# SW108_0713.net
KiCad netlist of a schematic drawn in Altium Designer
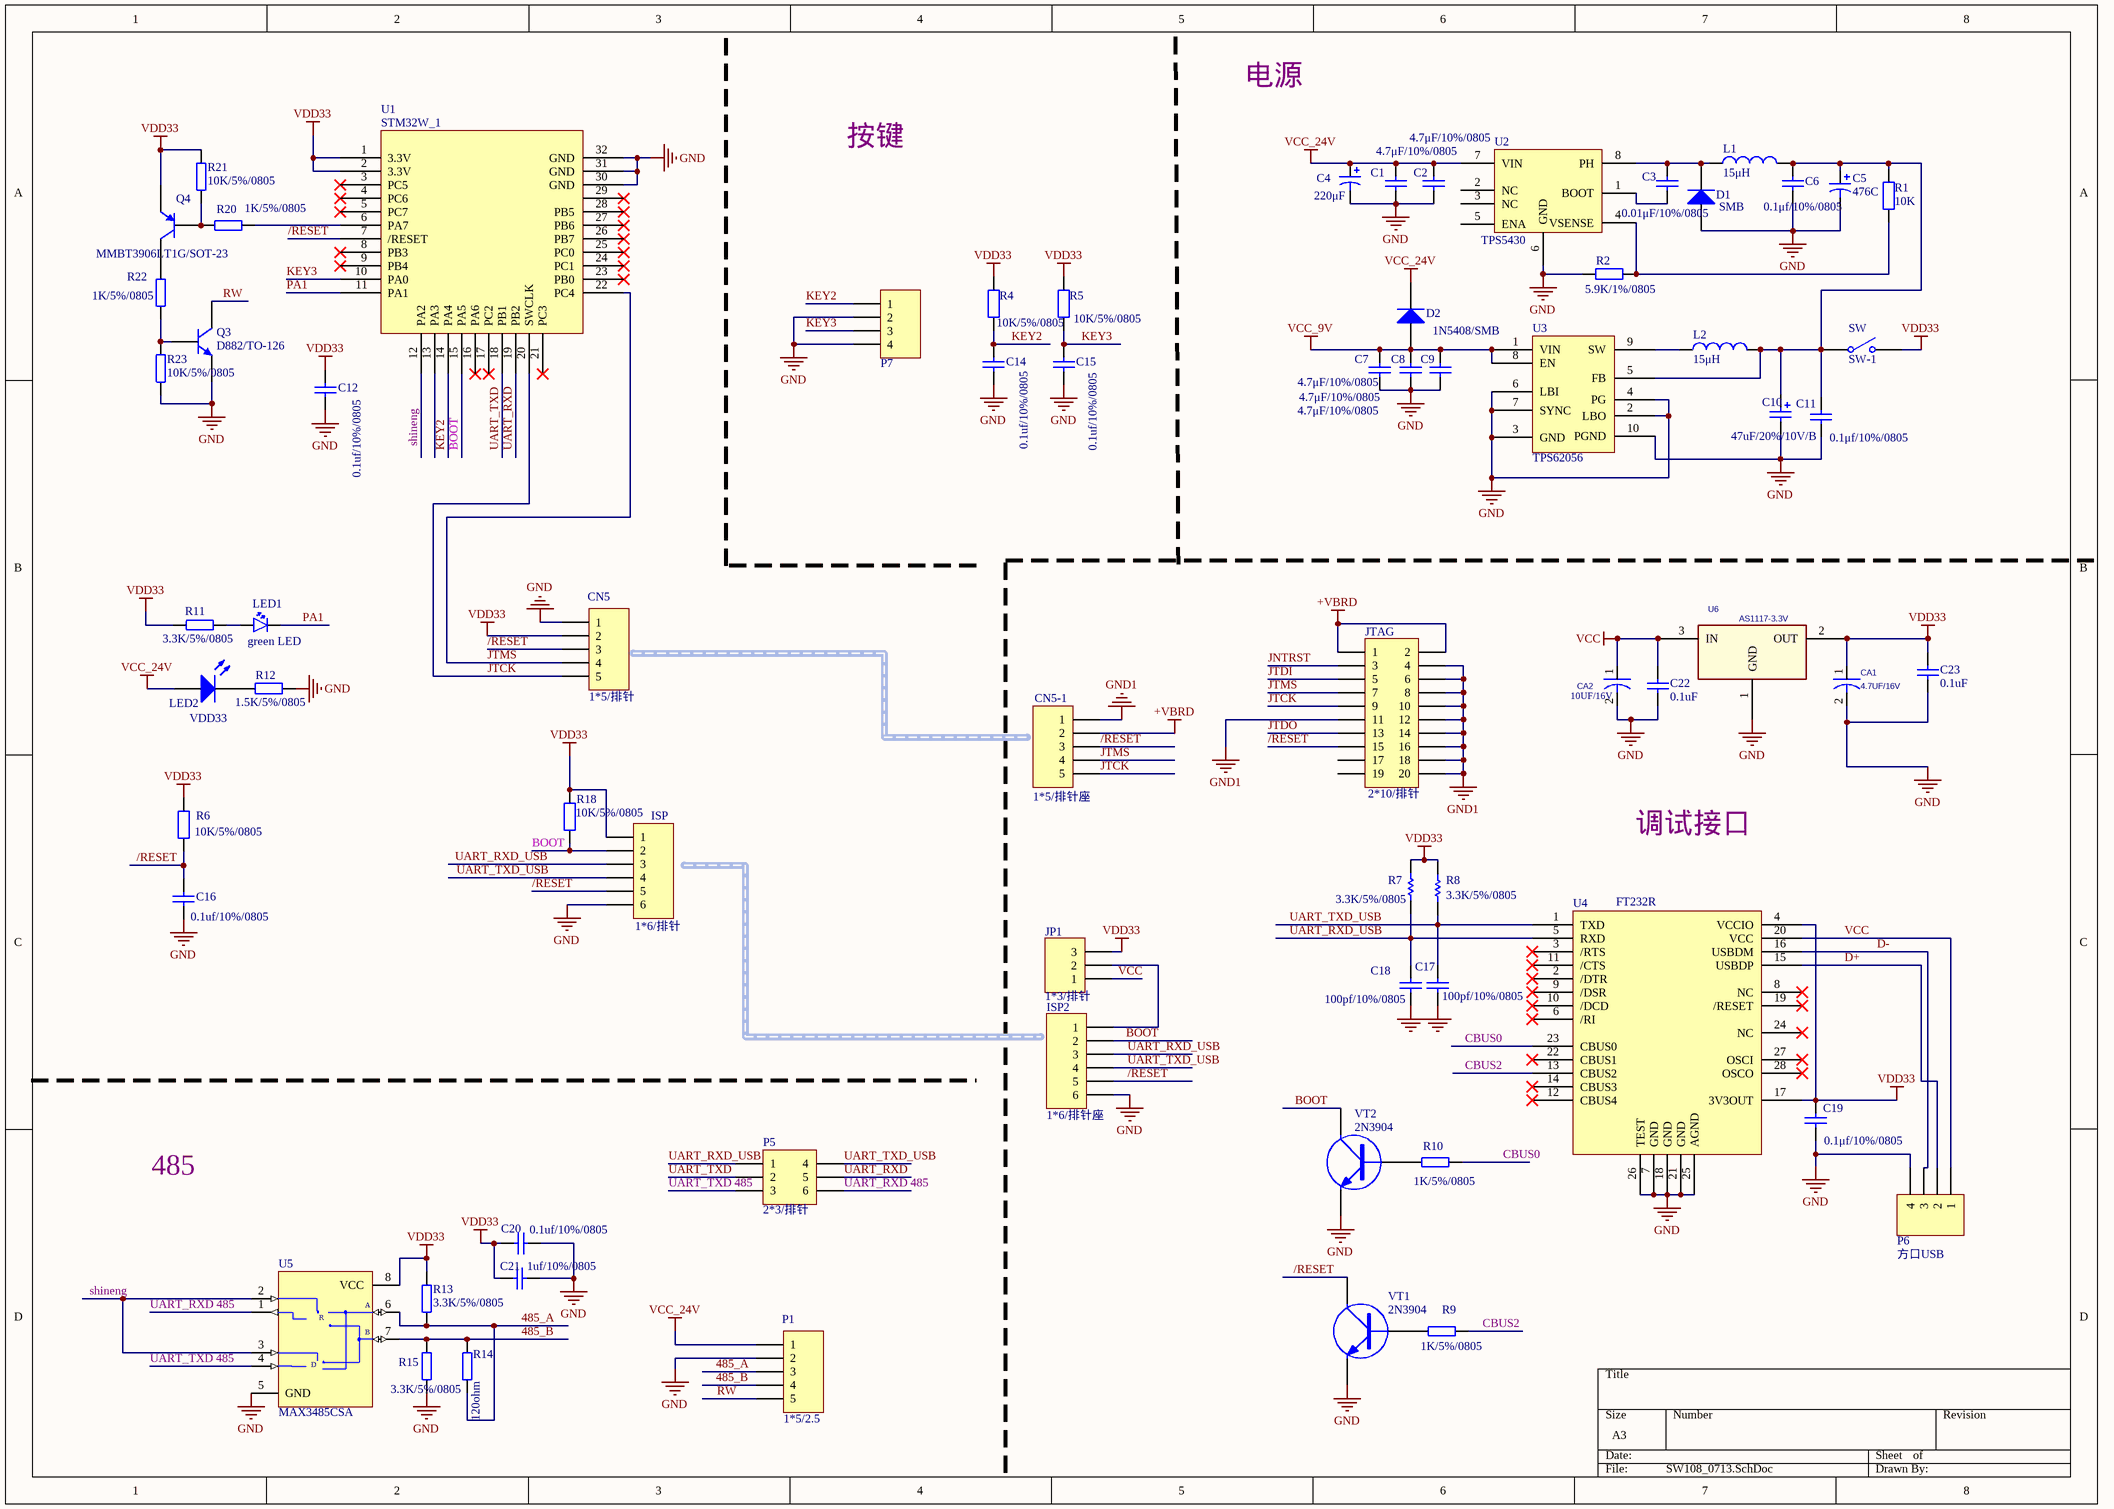
[diagram p0: SW108_0713.SchDoc]

(export (version "E")
  (design (tool "Eeschema 10.0.6"))
  (components
    (comp (ref "C1")
      (value "4.7μF/10%/0805")
      (footprint "C-0805")
      (description "Capacitor")
      (fields (field (name "PUBLISHER") "Altium Limited"))
      (libsource (lib "Miscellaneous Devices") (part "Cap"))
    )
    (comp (ref "C2")
      (value "4.7μF/10%/0805")
      (footprint "C-0805")
      (description "Capacitor")
      (fields (field (name "PUBLISHER") "Altium Limited"))
      (libsource (lib "Miscellaneous Devices") (part "Cap"))
    )
    (comp (ref "C3")
      (value "0.01μF/10%/0805")
      (footprint "C-0805")
      (description "Capacitor")
      (fields (field (name "PUBLISHER") "Altium Limited"))
      (libsource (lib "Miscellaneous Devices") (part "Cap"))
    )
    (comp (ref "C4")
      (value "220μF")
      (footprint "CZ3.0/6.5")
      (description "Polarized Capacitor (Radial)")
      (fields (field (name "PUBLISHER") "Altium Limited"))
      (libsource (lib "Miscellaneous Devices") (part "Cap Pol1"))
    )
    (comp (ref "C5")
      (value "476C")
      (footprint "C-TAN-D")
      (description "Polarized Capacitor (Radial)")
      (fields (field (name "PUBLISHER") "Altium Limited"))
      (libsource (lib "Miscellaneous Devices") (part "Cap Pol1"))
    )
    (comp (ref "C6")
      (value "0.1μf/10%/0805")
      (footprint "C-0805")
      (description "Capacitor")
      (fields (field (name "PUBLISHER") "Altium Limited"))
      (libsource (lib "Miscellaneous Devices") (part "Cap"))
    )
    (comp (ref "C7")
      (value "4.7μF/10%/0805")
      (footprint "C-0805")
      (description "Capacitor")
      (fields (field (name "PUBLISHER") "Altium Limited"))
      (libsource (lib "Miscellaneous Devices") (part "Cap"))
    )
    (comp (ref "C8")
      (value "4.7μF/10%/0805")
      (footprint "C-0805")
      (description "Capacitor")
      (fields (field (name "PUBLISHER") "Altium Limited"))
      (libsource (lib "Miscellaneous Devices") (part "Cap"))
    )
    (comp (ref "C9")
      (value "4.7μF/10%/0805")
      (footprint "C-0805")
      (description "Capacitor")
      (fields (field (name "PUBLISHER") "Altium Limited"))
      (libsource (lib "Miscellaneous Devices") (part "Cap"))
    )
    (comp (ref "C10")
      (value "47uF/20%/10V/B")
      (footprint "C-TAN-B")
      (libsource (lib "浙江关西电机数据库") (part "CAP_polarity"))
    )
    (comp (ref "C11")
      (value "0.1μf/10%/0805")
      (footprint "C-0805")
      (description "Capacitor")
      (fields (field (name "PUBLISHER") "Altium Limited"))
      (libsource (lib "Miscellaneous Devices") (part "Cap"))
    )
    (comp (ref "C12")
      (value "0.1uf/10%/0805")
      (footprint "C-0805")
      (description "Capacitor")
      (fields (field (name "PUBLISHER") "Altium Limited"))
      (libsource (lib "Miscellaneous Devices") (part "Cap"))
    )
    (comp (ref "C14")
      (value "0.1uf/10%/0805")
      (footprint "C-0805")
      (description "Capacitor")
      (fields (field (name "PUBLISHER") "Altium Limited"))
      (libsource (lib "Miscellaneous Devices") (part "Cap"))
    )
    (comp (ref "C15")
      (value "0.1uf/10%/0805")
      (footprint "C-0805")
      (description "Capacitor")
      (fields (field (name "PUBLISHER") "Altium Limited"))
      (libsource (lib "Miscellaneous Devices") (part "Cap"))
    )
    (comp (ref "C16")
      (value "0.1uf/10%/0805")
      (footprint "C-0805")
      (description "Capacitor")
      (fields (field (name "PUBLISHER") "Altium Limited"))
      (libsource (lib "Miscellaneous Devices") (part "Cap"))
    )
    (comp (ref "C17")
      (value "100pf/10%/0805")
      (footprint "C-0805")
      (description "Capacitor")
      (fields (field (name "PUBLISHER") "Altium Limited"))
      (libsource (lib "Miscellaneous Devices") (part "Cap"))
    )
    (comp (ref "C18")
      (value "100pf/10%/0805")
      (footprint "C-0805")
      (description "Capacitor")
      (fields (field (name "PUBLISHER") "Altium Limited"))
      (libsource (lib "Miscellaneous Devices") (part "Cap"))
    )
    (comp (ref "C19")
      (value "0.1μf/10%/0805")
      (footprint "C-0805")
      (description "Capacitor")
      (fields (field (name "PUBLISHER") "Altium Limited"))
      (libsource (lib "Miscellaneous Devices") (part "Cap"))
    )
    (comp (ref "C20")
      (value "0.1uf/10%/0805")
      (footprint "C-0805")
      (description "Capacitor")
      (fields (field (name "PUBLISHER") "Altium Limited"))
      (libsource (lib "Miscellaneous Devices") (part "Cap"))
    )
    (comp (ref "C21")
      (value "1uf/10%/0805")
      (footprint "C-0805")
      (description "Capacitor")
      (fields (field (name "PUBLISHER") "Altium Limited"))
      (libsource (lib "Miscellaneous Devices") (part "Cap"))
    )
    (comp (ref "C22")
      (value "0.1uF")
      (footprint "C0805")
      (description "Capacitor")
      (fields (field (name "PUBLISHER") "Altium Limited"))
      (libsource (lib "Miscellaneous Devices") (part "Cap"))
    )
    (comp (ref "C23")
      (value "0.1uF")
      (footprint "C0805")
      (description "Capacitor")
      (fields (field (name "PUBLISHER") "Altium Limited"))
      (libsource (lib "Miscellaneous Devices") (part "Cap"))
    )
    (comp (ref "CA1") (value "4.7UF/16V") (footprint "3528cap") (libsource (lib "v3") (part "ECAP")))
    (comp (ref "CA2") (value "10UF/16V") (footprint "3528Cap") (libsource (lib "v3") (part "ECAP")))
    (comp (ref "CN5") (value "1*5/排针") (footprint "PIN-S-2.54-1*5") (libsource (lib "") (part "Header1*5_1")))
    (comp (ref "CN5-1")
      (value "1*5/排针座")
      (footprint "PIN-S-2.54-1*5")
      (libsource (lib "SCHLIBRARIES") (part "Header1*5"))
    )
    (comp (ref "D1")
      (value "SMB")
      (footprint "SMB")
      (description "3 Amp Medium Power Silicon Rectifier Diode")
      (fields (field (name "PUBLISHER") "Altium Limited"))
      (libsource (lib "Miscellaneous Devices") (part "Diode 1N5408"))
    )
    (comp (ref "D2")
      (value "1N5408/SMB")
      (footprint "smb")
      (description "3 Amp Medium Power Silicon Rectifier Diode")
      (fields (field (name "PUBLISHER") "Altium Limited"))
      (libsource (lib "Miscellaneous Devices") (part "Diode 1N5408"))
    )
    (comp (ref "ISP")
      (value "1*6/排针")
      (footprint "PIN-S-2.54-1*6")
      (libsource (lib "SCHLIBRARIES") (part "Header1*6"))
    )
    (comp (ref "ISP2")
      (value "1*6/排针座")
      (footprint "PIN-S-2.54-1*6")
      (libsource (lib "") (part "Header1*6_1"))
    )
    (comp (ref "JP1")
      (value "1*3/排针")
      (footprint "PIN-S-2.54-1*3")
      (libsource (lib "SCHLIBRARIES") (part "Header1*3"))
    )
    (comp (ref "JTAG")
      (value "2*10/排针")
      (footprint "IDC-20")
      (libsource (lib "SCHLIBRARIES") (part "Header2*10"))
    )
    (comp (ref "L1")
      (value "15μH")
      (footprint "GSDS104C2")
      (description "Inductor")
      (fields (field (name "PUBLISHER") "Altium Limited"))
      (libsource (lib "Miscellaneous Devices") (part "Inductor"))
    )
    (comp (ref "L2")
      (value "15μH")
      (footprint "GSDS104C2")
      (description "Inductor")
      (fields (field (name "PUBLISHER") "Altium Limited"))
      (libsource (lib "Miscellaneous Devices") (part "Inductor"))
    )
    (comp (ref "LED1") (value "green LED") (footprint "LED-φ3") (libsource (lib "Haze") (part "LED")))
    (comp (ref "LED2")
      (value "VDD33")
      (footprint "LED-φ3")
      (description "Typical BLUE SiC LED")
      (fields (field (name "PUBLISHER") "Altium Limited"))
      (libsource (lib "Miscellaneous Devices") (part "LED3"))
    )
    (comp (ref "P1") (value "1*5/2.5") (footprint "PIN-S-2.54-1*5") (libsource (lib "") (part "Header1*5_1")))
    (comp (ref "P5")
      (value "2*3/排针")
      (footprint "HDR2X3_CEN")
      (description "Header, 3-Pin, Dual row")
      (fields (field (name "PUBLISHER") "Altium Limited"))
      (libsource (lib "Miscellaneous Connectors") (part "Header 3X2A"))
    )
    (comp (ref "P6")
      (value "方口USB")
      (footprint "USB_B_90D")
      (description "Header, 4-Pin")
      (fields (field (name "PUBLISHER") "Altium Limited"))
      (libsource (lib "Miscellaneous Connectors") (part "Header 4"))
    )
    (comp (ref "P7")
      (value "Header1*4")
      (footprint "PIN-S-2.54-1*4")
      (libsource (lib "SCHLIBRARIES") (part "Header1*4"))
    )
    (comp (ref "Q3")
      (value "D882/TO-126")
      (footprint "TO-126")
      (libsource (lib "SCHLIBRARIES") (part "NPN-1E2C3B"))
    )
    (comp (ref "Q4")
      (value "MMBT3906LT1G/SOT-23")
      (footprint "SOT-23")
      (fields (field (name "PART NUMBER") "ASQ-0009BA") (field (name "型号") "MMBT3906LT1G/SOT-23"))
      (libsource (lib "浙江关西电机数据库") (part "PNP_1B2E3C"))
    )
    (comp (ref "R1")
      (value "10K")
      (footprint "R-0805")
      (description "Resistor")
      (fields (field (name "PUBLISHER") "Altium Limited"))
      (libsource (lib "") (part "Res2_1"))
    )
    (comp (ref "R2")
      (value "5.9K/1%/0805")
      (footprint "R-0805")
      (description "Resistor")
      (fields (field (name "PUBLISHER") "Altium Limited"))
      (libsource (lib "Miscellaneous Devices") (part "Res2"))
    )
    (comp (ref "R4")
      (value "10K/5%/0805")
      (footprint "R-0805")
      (description "Resistor")
      (fields (field (name "PUBLISHER") "Altium Limited"))
      (libsource (lib "") (part "Res2_1"))
    )
    (comp (ref "R5")
      (value "10K/5%/0805")
      (footprint "R-0805")
      (description "Resistor")
      (fields (field (name "PUBLISHER") "Altium Limited"))
      (libsource (lib "") (part "Res2_1"))
    )
    (comp (ref "R6")
      (value "10K/5%/0805")
      (footprint "R-0805")
      (description "Resistor")
      (fields (field (name "PUBLISHER") "Altium Limited"))
      (libsource (lib "") (part "Res2_1"))
    )
    (comp (ref "R7")
      (value "3.3K/5%/0805")
      (footprint "R-0805")
      (libsource (lib "SCHLIBRARIES") (part "RES_1"))
    )
    (comp (ref "R8")
      (value "3.3K/5%/0805")
      (footprint "R-0805")
      (libsource (lib "SCHLIBRARIES") (part "RES_1"))
    )
    (comp (ref "R9")
      (value "1K/5%/0805")
      (footprint "R-0805")
      (description "R")
      (libsource (lib "Haze") (part "RES"))
    )
    (comp (ref "R10")
      (value "1K/5%/0805")
      (footprint "R-0805")
      (description "R")
      (libsource (lib "Haze") (part "RES"))
    )
    (comp (ref "R11")
      (value "3.3K/5%/0805")
      (footprint "R-0805")
      (description "R")
      (libsource (lib "Haze") (part "RES"))
    )
    (comp (ref "R12")
      (value "1.5K/5%/0805")
      (footprint "R-0805")
      (description "Resistor")
      (fields (field (name "PUBLISHER") "Altium Limited"))
      (libsource (lib "Miscellaneous Devices") (part "Res2"))
    )
    (comp (ref "R13")
      (value "3.3K/5%/0805")
      (footprint "R-0805")
      (description "R")
      (libsource (lib "Haze") (part "RES"))
    )
    (comp (ref "R14")
      (value "120ohm")
      (footprint "R-0805")
      (description "R")
      (libsource (lib "Haze") (part "RES"))
    )
    (comp (ref "R15")
      (value "3.3K/5%/0805")
      (footprint "R-0805")
      (description "R")
      (libsource (lib "Haze") (part "RES"))
    )
    (comp (ref "R18")
      (value "10K/5%/0805")
      (footprint "R-0805")
      (description "Resistor")
      (fields (field (name "PUBLISHER") "Altium Limited"))
      (libsource (lib "") (part "Res2_1"))
    )
    (comp (ref "R20")
      (value "1K/5%/0805")
      (footprint "R-0805")
      (description "R")
      (libsource (lib "Haze") (part "RES"))
    )
    (comp (ref "R21")
      (value "10K/5%/0805")
      (footprint "R-0805")
      (description "R")
      (libsource (lib "Haze") (part "RES"))
    )
    (comp (ref "R22")
      (value "1K/5%/0805")
      (footprint "R-0805")
      (description "R")
      (libsource (lib "Haze") (part "RES"))
    )
    (comp (ref "R23")
      (value "10K/5%/0805")
      (footprint "R-0805")
      (description "R")
      (libsource (lib "Haze") (part "RES"))
    )
    (comp (ref "SW")
      (value "SW-1")
      (footprint "PIN-S-2.54-1*2")
      (libsource (lib "SCHLIBRARIES") (part "SW-1"))
    )
    (comp (ref "U1")
      (value "STM32W_1")
      (footprint "STM32W108-3")
      (libsource (lib "STM32W108-3") (part "STM32W108-3"))
    )
    (comp (ref "U2") (value "TPS5430") (footprint "SO-G8") (libsource (lib "SCHLIBRARIES") (part "TPS5430")))
    (comp (ref "U3")
      (value "TPS62056")
      (footprint "MSOP-10")
      (libsource (lib "SCHLIBRARIES") (part "TPS62056"))
    )
    (comp (ref "U4") (value "FT232R") (footprint "SSOP-28") (libsource (lib "Haze") (part "FT232R")))
    (comp (ref "U5")
      (value "MAX3485CSA")
      (footprint "SO-G8")
      (description "Low-Power, Slew-Rate-Limited RS-485/RS-422 Transceiver")
      (fields (field (name "PUBLISHER") "Altium Limited"))
      (libsource (lib "Maxim Communication Transceiver") (part "MAX485CSA"))
    )
    (comp (ref "U6") (value "AS1117-3.3V") (footprint "SOT-223") (libsource (lib "v3") (part "AS1117")))
    (comp (ref "VT1")
      (value "2N3904")
      (footprint "SOT23-3")
      (description "NPN Transistor")
      (libsource (lib "Haze") (part "NPN"))
    )
    (comp (ref "VT2")
      (value "2N3904")
      (footprint "SOT23-3")
      (description "NPN Transistor")
      (libsource (lib "Haze") (part "NPN"))
    )
  )
  (nets
    (net (code "1") (name "+VBRD") (class "Default")
      (node (ref "CN5-1") (pin "2") (pinfunction "2_2") (pintype "passive"))
      (node (ref "JTAG") (pin "1") (pinfunction "1_1") (pintype "passive"))
      (node (ref "JTAG") (pin "2") (pinfunction "2_2") (pintype "passive"))
    )
    (net (code "2") (name "/485_A") (class "Default")
      (node (ref "P1") (pin "3") (pinfunction "3_3") (pintype "passive"))
      (node (ref "R13") (pin "1") (pinfunction "1_1") (pintype "passive"))
      (node (ref "R14") (pin "2") (pinfunction "2_2") (pintype "passive"))
      (node (ref "U5") (pin "6") (pinfunction "A_6") (pintype "bidirectional"))
    )
    (net (code "3") (name "/485_B") (class "Default")
      (node (ref "P1") (pin "4") (pinfunction "4_4") (pintype "passive"))
      (node (ref "R14") (pin "1") (pinfunction "1_1") (pintype "passive"))
      (node (ref "R15") (pin "2") (pinfunction "2_2") (pintype "passive"))
      (node (ref "U5") (pin "7") (pinfunction "B_7") (pintype "bidirectional"))
    )
    (net (code "4") (name "/BOOT") (class "Default")
      (node (ref "ISP") (pin "2") (pinfunction "2_2") (pintype "passive"))
      (node (ref "ISP2") (pin "2") (pinfunction "2_2") (pintype "passive"))
      (node (ref "R18") (pin "1") (pinfunction "1_1") (pintype "passive"))
      (node (ref "U1") (pin "15") (pinfunction "PA5_15") (pintype "passive"))
      (node (ref "VT2") (pin "3") (pinfunction "C_3") (pintype "passive"))
    )
    (net (code "5") (name "/CBUS0") (class "Default")
      (node (ref "R10") (pin "2") (pinfunction "2_2") (pintype "passive"))
      (node (ref "U4") (pin "23") (pinfunction "CBUS0_23") (pintype "passive"))
    )
    (net (code "6") (name "/CBUS2") (class "Default")
      (node (ref "R9") (pin "2") (pinfunction "2_2") (pintype "passive"))
      (node (ref "U4") (pin "13") (pinfunction "CBUS2_13") (pintype "passive"))
    )
    (net (code "7") (name "/D+") (class "Default")
      (node (ref "P6") (pin "2") (pinfunction "2_2") (pintype "passive"))
      (node (ref "U4") (pin "15") (pinfunction "USBDP_15") (pintype "passive"))
    )
    (net (code "8") (name "/D-") (class "Default")
      (node (ref "P6") (pin "3") (pinfunction "3_3") (pintype "passive"))
      (node (ref "U4") (pin "16") (pinfunction "USBDM_16") (pintype "passive"))
    )
    (net (code "9") (name "/JNTRST") (class "Default")
      (node (ref "JTAG") (pin "3") (pinfunction "3_3") (pintype "passive"))
    )
    (net (code "10") (name "/JTCK") (class "Default")
      (node (ref "CN5") (pin "5") (pinfunction "5_5") (pintype "passive"))
      (node (ref "CN5-1") (pin "5") (pinfunction "5_5") (pintype "passive"))
      (node (ref "JTAG") (pin "9") (pinfunction "9_9") (pintype "passive"))
      (node (ref "U1") (pin "20") (pinfunction "SWCLK_20") (pintype "passive"))
    )
    (net (code "11") (name "/JTDI") (class "Default")
      (node (ref "JTAG") (pin "5") (pinfunction "5_5") (pintype "passive"))
    )
    (net (code "12") (name "/JTDO") (class "Default")
      (node (ref "JTAG") (pin "13") (pinfunction "13_13") (pintype "passive"))
    )
    (net (code "13") (name "/JTMS") (class "Default")
      (node (ref "CN5") (pin "4") (pinfunction "4_4") (pintype "passive"))
      (node (ref "CN5-1") (pin "4") (pinfunction "4_4") (pintype "passive"))
      (node (ref "JTAG") (pin "7") (pinfunction "7_7") (pintype "passive"))
      (node (ref "U1") (pin "22") (pinfunction "PC4_22") (pintype "passive"))
    )
    (net (code "14") (name "/KEY2") (class "Default")
      (node (ref "C14") (pin "2") (pinfunction "2_2") (pintype "passive"))
      (node (ref "P7") (pin "1") (pinfunction "1_1") (pintype "passive"))
      (node (ref "R4") (pin "1") (pinfunction "1_1") (pintype "passive"))
      (node (ref "U1") (pin "14") (pinfunction "PA4_14") (pintype "passive"))
    )
    (net (code "15") (name "/KEY3") (class "Default")
      (node (ref "C15") (pin "2") (pinfunction "2_2") (pintype "passive"))
      (node (ref "P7") (pin "3") (pinfunction "3_3") (pintype "passive"))
      (node (ref "R5") (pin "1") (pinfunction "1_1") (pintype "passive"))
      (node (ref "U1") (pin "10") (pinfunction "PA0_10") (pintype "passive"))
    )
    (net (code "16") (name "/PA1") (class "Default")
      (node (ref "LED1") (pin "2") (pinfunction "K_2") (pintype "passive"))
      (node (ref "U1") (pin "11") (pinfunction "PA1_11") (pintype "passive"))
    )
    (net (code "17") (name "/RW") (class "Default")
      (node (ref "P1") (pin "5") (pinfunction "5_5") (pintype "passive"))
      (node (ref "Q3") (pin "2") (pinfunction "C_2") (pintype "passive"))
    )
    (net (code "18") (name "/UART_RXD") (class "Default")
      (node (ref "P5") (pin "5") (pinfunction "5_5") (pintype "passive"))
      (node (ref "U1") (pin "19") (pinfunction "PB2_19") (pintype "passive"))
    )
    (net (code "19") (name "/UART_RXD 485") (class "Default")
      (node (ref "P5") (pin "6") (pinfunction "6_6") (pintype "passive"))
      (node (ref "U5") (pin "1") (pinfunction "RO_1") (pintype "output"))
    )
    (net (code "20") (name "/UART_RXD_USB") (class "Default")
      (node (ref "C18") (pin "2") (pinfunction "2_2") (pintype "passive"))
      (node (ref "ISP") (pin "3") (pinfunction "3_3") (pintype "passive"))
      (node (ref "ISP2") (pin "3") (pinfunction "3_3") (pintype "passive"))
      (node (ref "P5") (pin "1") (pinfunction "1_1") (pintype "passive"))
      (node (ref "R7") (pin "1") (pinfunction "1_1") (pintype "passive"))
      (node (ref "U4") (pin "5") (pinfunction "RXD_5") (pintype "passive"))
    )
    (net (code "21") (name "/UART_TXD") (class "Default")
      (node (ref "P5") (pin "2") (pinfunction "2_2") (pintype "passive"))
      (node (ref "U1") (pin "18") (pinfunction "PB1_18") (pintype "passive"))
    )
    (net (code "22") (name "/UART_TXD 485") (class "Default")
      (node (ref "P5") (pin "3") (pinfunction "3_3") (pintype "passive"))
      (node (ref "U5") (pin "4") (pinfunction "DI_4") (pintype "input"))
    )
    (net (code "23") (name "/UART_TXD_USB") (class "Default")
      (node (ref "C17") (pin "2") (pinfunction "2_2") (pintype "passive"))
      (node (ref "ISP") (pin "4") (pinfunction "4_4") (pintype "passive"))
      (node (ref "ISP2") (pin "4") (pinfunction "4_4") (pintype "passive"))
      (node (ref "P5") (pin "4") (pinfunction "4_4") (pintype "passive"))
      (node (ref "R8") (pin "1") (pinfunction "1_1") (pintype "passive"))
      (node (ref "U4") (pin "1") (pinfunction "TXD_1") (pintype "passive"))
    )
    (net (code "24") (name "/shineng") (class "Default")
      (node (ref "U1") (pin "12") (pinfunction "PA2_12") (pintype "passive"))
      (node (ref "U5") (pin "2") (pinfunction "~{RE}_2") (pintype "input"))
      (node (ref "U5") (pin "3") (pinfunction "DE_3") (pintype "input"))
    )
    (net (code "25") (name "/{slash}RESET") (class "Default")
      (node (ref "C16") (pin "2") (pinfunction "2_2") (pintype "passive"))
      (node (ref "CN5") (pin "3") (pinfunction "3_3") (pintype "passive"))
      (node (ref "CN5-1") (pin "3") (pinfunction "3_3") (pintype "passive"))
      (node (ref "ISP") (pin "5") (pinfunction "5_5") (pintype "passive"))
      (node (ref "ISP2") (pin "5") (pinfunction "5_5") (pintype "passive"))
      (node (ref "JTAG") (pin "15") (pinfunction "15_15") (pintype "passive"))
      (node (ref "R6") (pin "1") (pinfunction "1_1") (pintype "passive"))
      (node (ref "U1") (pin "7") (pinfunction "/RESET_7") (pintype "passive"))
      (node (ref "VT1") (pin "3") (pinfunction "C_3") (pintype "passive"))
    )
    (net (code "26") (name "GND") (class "Default")
      (node (ref "C1") (pin "1") (pinfunction "1_1") (pintype "passive"))
      (node (ref "C10") (pin "2") (pinfunction "2_2") (pintype "passive"))
      (node (ref "C11") (pin "1") (pinfunction "1_1") (pintype "passive"))
      (node (ref "C12") (pin "1") (pinfunction "1_1") (pintype "passive"))
      (node (ref "C14") (pin "1") (pinfunction "1_1") (pintype "passive"))
      (node (ref "C15") (pin "1") (pinfunction "1_1") (pintype "passive"))
      (node (ref "C16") (pin "1") (pinfunction "1_1") (pintype "passive"))
      (node (ref "C17") (pin "1") (pinfunction "1_1") (pintype "passive"))
      (node (ref "C18") (pin "1") (pinfunction "1_1") (pintype "passive"))
      (node (ref "C19") (pin "1") (pinfunction "1_1") (pintype "passive"))
      (node (ref "C2") (pin "1") (pinfunction "1_1") (pintype "passive"))
      (node (ref "C20") (pin "1") (pinfunction "1_1") (pintype "passive"))
      (node (ref "C21") (pin "1") (pinfunction "1_1") (pintype "passive"))
      (node (ref "C22") (pin "1") (pinfunction "1_1") (pintype "passive"))
      (node (ref "C23") (pin "1") (pinfunction "1_1") (pintype "passive"))
      (node (ref "C4") (pin "2") (pinfunction "2_2") (pintype "passive"))
      (node (ref "C5") (pin "2") (pinfunction "2_2") (pintype "passive"))
      (node (ref "C6") (pin "1") (pinfunction "1_1") (pintype "passive"))
      (node (ref "C7") (pin "1") (pinfunction "1_1") (pintype "passive"))
      (node (ref "C8") (pin "1") (pinfunction "1_1") (pintype "passive"))
      (node (ref "C9") (pin "1") (pinfunction "1_1") (pintype "passive"))
      (node (ref "CA1") (pin "2") (pinfunction "2_2") (pintype "passive"))
      (node (ref "CA2") (pin "2") (pinfunction "2_2") (pintype "passive"))
      (node (ref "CN5") (pin "1") (pinfunction "1_1") (pintype "passive"))
      (node (ref "D1") (pin "1") (pinfunction "A_1") (pintype "passive"))
      (node (ref "ISP") (pin "6") (pinfunction "6_6") (pintype "passive"))
      (node (ref "ISP2") (pin "6") (pinfunction "6_6") (pintype "passive"))
      (node (ref "P1") (pin "2") (pinfunction "2_2") (pintype "passive"))
      (node (ref "P6") (pin "4") (pinfunction "4_4") (pintype "passive"))
      (node (ref "P7") (pin "2") (pinfunction "2_2") (pintype "passive"))
      (node (ref "P7") (pin "4") (pinfunction "4_4") (pintype "passive"))
      (node (ref "Q3") (pin "1") (pinfunction "E_1") (pintype "passive"))
      (node (ref "R12") (pin "1") (pinfunction "1_1") (pintype "passive"))
      (node (ref "R15") (pin "1") (pinfunction "1_1") (pintype "passive"))
      (node (ref "R2") (pin "2") (pinfunction "2_2") (pintype "passive"))
      (node (ref "R23") (pin "1") (pinfunction "1_1") (pintype "passive"))
      (node (ref "U1") (pin "30") (pinfunction "GND_30") (pintype "passive"))
      (node (ref "U1") (pin "31") (pinfunction "GND_31") (pintype "passive"))
      (node (ref "U1") (pin "32") (pinfunction "GND_32") (pintype "passive"))
      (node (ref "U2") (pin "6") (pinfunction "GND_6") (pintype "passive"))
      (node (ref "U3") (pin "10") (pinfunction "PGND_10") (pintype "passive"))
      (node (ref "U3") (pin "2") (pinfunction "LBO_2") (pintype "passive"))
      (node (ref "U3") (pin "3") (pinfunction "GND_3") (pintype "passive"))
      (node (ref "U3") (pin "4") (pinfunction "PG_4") (pintype "passive"))
      (node (ref "U3") (pin "6") (pinfunction "LBI_6") (pintype "passive"))
      (node (ref "U3") (pin "7") (pinfunction "SYNC_7") (pintype "passive"))
      (node (ref "U4") (pin "18") (pinfunction "GND_18") (pintype "passive"))
      (node (ref "U4") (pin "21") (pinfunction "GND_21") (pintype "passive"))
      (node (ref "U4") (pin "25") (pinfunction "AGND_25") (pintype "passive"))
      (node (ref "U4") (pin "26") (pinfunction "TEST_26") (pintype "passive"))
      (node (ref "U4") (pin "7") (pinfunction "GND_7") (pintype "passive"))
      (node (ref "U5") (pin "5") (pinfunction "GND_5") (pintype "power_in"))
      (node (ref "U6") (pin "1") (pinfunction "GND_1") (pintype "passive"))
      (node (ref "VT1") (pin "2") (pinfunction "E_2") (pintype "passive"))
      (node (ref "VT2") (pin "2") (pinfunction "E_2") (pintype "passive"))
    )
    (net (code "27") (name "GND1") (class "Default")
      (node (ref "CN5-1") (pin "1") (pinfunction "1_1") (pintype "passive"))
      (node (ref "JTAG") (pin "10") (pinfunction "10_10") (pintype "passive"))
      (node (ref "JTAG") (pin "11") (pinfunction "11_11") (pintype "passive"))
      (node (ref "JTAG") (pin "12") (pinfunction "12_12") (pintype "passive"))
      (node (ref "JTAG") (pin "14") (pinfunction "14_14") (pintype "passive"))
      (node (ref "JTAG") (pin "16") (pinfunction "16_16") (pintype "passive"))
      (node (ref "JTAG") (pin "18") (pinfunction "18_18") (pintype "passive"))
      (node (ref "JTAG") (pin "20") (pinfunction "20_20") (pintype "passive"))
      (node (ref "JTAG") (pin "4") (pinfunction "4_4") (pintype "passive"))
      (node (ref "JTAG") (pin "6") (pinfunction "6_6") (pintype "passive"))
      (node (ref "JTAG") (pin "8") (pinfunction "8_8") (pintype "passive"))
    )
    (net (code "28") (name "Net-(D1-K)") (class "Default")
      (node (ref "C3") (pin "2") (pinfunction "2_2") (pintype "passive"))
      (node (ref "D1") (pin "2") (pinfunction "K_2") (pintype "passive"))
      (node (ref "L1") (pin "1") (pinfunction "1_1") (pintype "passive"))
      (node (ref "U2") (pin "8") (pinfunction "PH_8") (pintype "passive"))
    )
    (net (code "29") (name "Net-(ISP2-Pad1)") (class "Default")
      (node (ref "ISP2") (pin "1") (pinfunction "1_1") (pintype "passive"))
      (node (ref "JP1") (pin "2") (pinfunction "2_2") (pintype "passive"))
    )
    (net (code "30") (name "Net-(LED1-A)") (class "Default")
      (node (ref "LED1") (pin "1") (pinfunction "A_1") (pintype "passive"))
      (node (ref "R11") (pin "2") (pinfunction "2_2") (pintype "passive"))
    )
    (net (code "31") (name "Net-(LED2-K)") (class "Default")
      (node (ref "LED2") (pin "2") (pinfunction "K_2") (pintype "passive"))
      (node (ref "R12") (pin "2") (pinfunction "2_2") (pintype "passive"))
    )
    (net (code "32") (name "Net-(Q3-B)") (class "Default")
      (node (ref "Q3") (pin "3") (pinfunction "B_3") (pintype "passive"))
      (node (ref "R22") (pin "1") (pinfunction "1_1") (pintype "passive"))
      (node (ref "R23") (pin "2") (pinfunction "2_2") (pintype "passive"))
    )
    (net (code "33") (name "Net-(Q4-B)") (class "Default")
      (node (ref "Q4") (pin "1") (pinfunction "B_1") (pintype "passive"))
      (node (ref "R20") (pin "1") (pinfunction "1_1") (pintype "passive"))
      (node (ref "R21") (pin "1") (pinfunction "1_1") (pintype "passive"))
    )
    (net (code "34") (name "Net-(Q4-C)") (class "Default")
      (node (ref "Q4") (pin "3") (pinfunction "C_3") (pintype "passive"))
      (node (ref "R22") (pin "2") (pinfunction "2_2") (pintype "passive"))
    )
    (net (code "35") (name "Net-(U1-PA7)") (class "Default")
      (node (ref "R20") (pin "2") (pinfunction "2_2") (pintype "passive"))
      (node (ref "U1") (pin "6") (pinfunction "PA7_6") (pintype "passive"))
    )
    (net (code "36") (name "Net-(U2-BOOT)") (class "Default")
      (node (ref "C3") (pin "1") (pinfunction "1_1") (pintype "passive"))
      (node (ref "U2") (pin "1") (pinfunction "BOOT_1") (pintype "passive"))
    )
    (net (code "37") (name "Net-(U2-VSENSE)") (class "Default")
      (node (ref "R1") (pin "1") (pinfunction "1_1") (pintype "passive"))
      (node (ref "R2") (pin "1") (pinfunction "1_1") (pintype "passive"))
      (node (ref "U2") (pin "4") (pinfunction "VSENSE_4") (pintype "passive"))
    )
    (net (code "38") (name "Net-(U3-FB)") (class "Default")
      (node (ref "C10") (pin "1") (pinfunction "1_1") (pintype "passive"))
      (node (ref "C11") (pin "2") (pinfunction "2_2") (pintype "passive"))
      (node (ref "C5") (pin "1") (pinfunction "1_1") (pintype "passive"))
      (node (ref "C6") (pin "2") (pinfunction "2_2") (pintype "passive"))
      (node (ref "L1") (pin "2") (pinfunction "2_2") (pintype "passive"))
      (node (ref "L2") (pin "2") (pinfunction "2_2") (pintype "passive"))
      (node (ref "R1") (pin "2") (pinfunction "2_2") (pintype "passive"))
      (node (ref "SW") (pin "1") (pinfunction "1_1") (pintype "passive"))
      (node (ref "U3") (pin "5") (pinfunction "FB_5") (pintype "passive"))
    )
    (net (code "39") (name "Net-(U3-SW)") (class "Default")
      (node (ref "L2") (pin "1") (pinfunction "1_1") (pintype "passive"))
      (node (ref "U3") (pin "9") (pinfunction "SW_9") (pintype "passive"))
    )
    (net (code "40") (name "Net-(VT1-B)") (class "Default")
      (node (ref "R9") (pin "1") (pinfunction "1_1") (pintype "passive"))
      (node (ref "VT1") (pin "1") (pinfunction "B_1") (pintype "passive"))
    )
    (net (code "41") (name "Net-(VT2-B)") (class "Default")
      (node (ref "R10") (pin "1") (pinfunction "1_1") (pintype "passive"))
      (node (ref "VT2") (pin "1") (pinfunction "B_1") (pintype "passive"))
    )
    (net (code "42") (name "VCC") (class "Default")
      (node (ref "C22") (pin "2") (pinfunction "2_2") (pintype "passive"))
      (node (ref "CA2") (pin "1") (pinfunction "1_1") (pintype "passive"))
      (node (ref "JP1") (pin "1") (pinfunction "1_1") (pintype "passive"))
      (node (ref "P6") (pin "1") (pinfunction "1_1") (pintype "passive"))
      (node (ref "U4") (pin "20") (pinfunction "VCC_20") (pintype "passive"))
      (node (ref "U6") (pin "3") (pinfunction "IN_3") (pintype "passive"))
    )
    (net (code "43") (name "VCC_9V") (class "Default")
      (node (ref "C7") (pin "2") (pinfunction "2_2") (pintype "passive"))
      (node (ref "C8") (pin "2") (pinfunction "2_2") (pintype "passive"))
      (node (ref "C9") (pin "2") (pinfunction "2_2") (pintype "passive"))
      (node (ref "D2") (pin "1") (pinfunction "A_1") (pintype "passive"))
      (node (ref "U3") (pin "1") (pinfunction "VIN_1") (pintype "passive"))
      (node (ref "U3") (pin "8") (pinfunction "EN_8") (pintype "passive"))
    )
    (net (code "44") (name "VCC_24V") (class "Default")
      (node (ref "C1") (pin "2") (pinfunction "2_2") (pintype "passive"))
      (node (ref "C2") (pin "2") (pinfunction "2_2") (pintype "passive"))
      (node (ref "C4") (pin "1") (pinfunction "1_1") (pintype "passive"))
      (node (ref "D2") (pin "2") (pinfunction "K_2") (pintype "passive"))
      (node (ref "LED2") (pin "1") (pinfunction "A_1") (pintype "passive"))
      (node (ref "P1") (pin "1") (pinfunction "1_1") (pintype "passive"))
      (node (ref "U2") (pin "7") (pinfunction "VIN_7") (pintype "passive"))
    )
    (net (code "45") (name "VDD33") (class "Default")
      (node (ref "C12") (pin "2") (pinfunction "2_2") (pintype "passive"))
      (node (ref "C19") (pin "2") (pinfunction "2_2") (pintype "passive"))
      (node (ref "C20") (pin "2") (pinfunction "2_2") (pintype "passive"))
      (node (ref "C21") (pin "2") (pinfunction "2_2") (pintype "passive"))
      (node (ref "C23") (pin "2") (pinfunction "2_2") (pintype "passive"))
      (node (ref "CA1") (pin "1") (pinfunction "1_1") (pintype "passive"))
      (node (ref "CN5") (pin "2") (pinfunction "2_2") (pintype "passive"))
      (node (ref "ISP") (pin "1") (pinfunction "1_1") (pintype "passive"))
      (node (ref "JP1") (pin "3") (pinfunction "3_3") (pintype "passive"))
      (node (ref "Q4") (pin "2") (pinfunction "E_2") (pintype "passive"))
      (node (ref "R11") (pin "1") (pinfunction "1_1") (pintype "passive"))
      (node (ref "R13") (pin "2") (pinfunction "2_2") (pintype "passive"))
      (node (ref "R18") (pin "2") (pinfunction "2_2") (pintype "passive"))
      (node (ref "R21") (pin "2") (pinfunction "2_2") (pintype "passive"))
      (node (ref "R4") (pin "2") (pinfunction "2_2") (pintype "passive"))
      (node (ref "R5") (pin "2") (pinfunction "2_2") (pintype "passive"))
      (node (ref "R6") (pin "2") (pinfunction "2_2") (pintype "passive"))
      (node (ref "R7") (pin "2") (pinfunction "2_2") (pintype "passive"))
      (node (ref "R8") (pin "2") (pinfunction "2_2") (pintype "passive"))
      (node (ref "SW") (pin "2") (pinfunction "2_2") (pintype "passive"))
      (node (ref "U1") (pin "1") (pinfunction "3.3V_1") (pintype "passive"))
      (node (ref "U1") (pin "2") (pinfunction "3.3V_2") (pintype "passive"))
      (node (ref "U4") (pin "17") (pinfunction "3V3OUT_17") (pintype "passive"))
      (node (ref "U4") (pin "4") (pinfunction "VCCIO_4") (pintype "passive"))
      (node (ref "U5") (pin "8") (pinfunction "VCC_8") (pintype "power_in"))
      (node (ref "U6") (pin "2") (pinfunction "OUT_2") (pintype "passive"))
    )
    (net (code "46") (name "unconnected-(JTAG-Pad17)") (class "Default")
      (node (ref "JTAG") (pin "17") (pinfunction "17_17") (pintype "passive"))
    )
    (net (code "47") (name "unconnected-(JTAG-Pad19)") (class "Default")
      (node (ref "JTAG") (pin "19") (pinfunction "19_19") (pintype "passive"))
    )
    (net (code "48") (name "unconnected-(U1-PA3-Pad13)") (class "Default")
      (node (ref "U1") (pin "13") (pinfunction "PA3_13") (pintype "passive"))
    )
    (net (code "49") (name "unconnected-(U1-PA6-Pad16)") (class "Default")
      (node (ref "U1") (pin "16") (pinfunction "PA6_16") (pintype "passive+no_connect"))
    )
    (net (code "50") (name "unconnected-(U1-PB0-Pad23)") (class "Default")
      (node (ref "U1") (pin "23") (pinfunction "PB0_23") (pintype "passive+no_connect"))
    )
    (net (code "51") (name "unconnected-(U1-PB3-Pad8)") (class "Default")
      (node (ref "U1") (pin "8") (pinfunction "PB3_8") (pintype "passive+no_connect"))
    )
    (net (code "52") (name "unconnected-(U1-PB4-Pad9)") (class "Default")
      (node (ref "U1") (pin "9") (pinfunction "PB4_9") (pintype "passive+no_connect"))
    )
    (net (code "53") (name "unconnected-(U1-PB5-Pad28)") (class "Default")
      (node (ref "U1") (pin "28") (pinfunction "PB5_28") (pintype "passive+no_connect"))
    )
    (net (code "54") (name "unconnected-(U1-PB6-Pad27)") (class "Default")
      (node (ref "U1") (pin "27") (pinfunction "PB6_27") (pintype "passive+no_connect"))
    )
    (net (code "55") (name "unconnected-(U1-PB7-Pad26)") (class "Default")
      (node (ref "U1") (pin "26") (pinfunction "PB7_26") (pintype "passive+no_connect"))
    )
    (net (code "56") (name "unconnected-(U1-PC0-Pad25)") (class "Default")
      (node (ref "U1") (pin "25") (pinfunction "PC0_25") (pintype "passive+no_connect"))
    )
    (net (code "57") (name "unconnected-(U1-PC1-Pad24)") (class "Default")
      (node (ref "U1") (pin "24") (pinfunction "PC1_24") (pintype "passive+no_connect"))
    )
    (net (code "58") (name "unconnected-(U1-PC2-Pad17)") (class "Default")
      (node (ref "U1") (pin "17") (pinfunction "PC2_17") (pintype "passive+no_connect"))
    )
    (net (code "59") (name "unconnected-(U1-PC3-Pad21)") (class "Default")
      (node (ref "U1") (pin "21") (pinfunction "PC3_21") (pintype "passive+no_connect"))
    )
    (net (code "60") (name "unconnected-(U1-PC5-Pad3)") (class "Default")
      (node (ref "U1") (pin "3") (pinfunction "PC5_3") (pintype "passive+no_connect"))
    )
    (net (code "61") (name "unconnected-(U1-PC6-Pad4)") (class "Default")
      (node (ref "U1") (pin "4") (pinfunction "PC6_4") (pintype "passive+no_connect"))
    )
    (net (code "62") (name "unconnected-(U1-PC7-Pad5)") (class "Default")
      (node (ref "U1") (pin "5") (pinfunction "PC7_5") (pintype "passive+no_connect"))
    )
    (net (code "63") (name "unconnected-(U1-Pad29)") (class "Default")
      (node (ref "U1") (pin "29") (pintype "passive+no_connect"))
    )
    (net (code "64") (name "unconnected-(U2-ENA-Pad5)") (class "Default")
      (node (ref "U2") (pin "5") (pinfunction "ENA_5") (pintype "passive"))
    )
    (net (code "65") (name "unconnected-(U2-NC-Pad2)") (class "Default")
      (node (ref "U2") (pin "2") (pinfunction "NC_2") (pintype "passive"))
    )
    (net (code "66") (name "unconnected-(U2-NC-Pad3)") (class "Default")
      (node (ref "U2") (pin "3") (pinfunction "NC_3") (pintype "passive"))
    )
    (net (code "67") (name "unconnected-(U4-CBUS1-Pad22)") (class "Default")
      (node (ref "U4") (pin "22") (pinfunction "CBUS1_22") (pintype "passive+no_connect"))
    )
    (net (code "68") (name "unconnected-(U4-CBUS3-Pad14)") (class "Default")
      (node (ref "U4") (pin "14") (pinfunction "CBUS3_14") (pintype "passive+no_connect"))
    )
    (net (code "69") (name "unconnected-(U4-CBUS4-Pad12)") (class "Default")
      (node (ref "U4") (pin "12") (pinfunction "CBUS4_12") (pintype "passive+no_connect"))
    )
    (net (code "70") (name "unconnected-(U4-NC-Pad8)") (class "Default")
      (node (ref "U4") (pin "8") (pinfunction "NC_8") (pintype "passive+no_connect"))
    )
    (net (code "71") (name "unconnected-(U4-NC-Pad24)") (class "Default")
      (node (ref "U4") (pin "24") (pinfunction "NC_24") (pintype "passive+no_connect"))
    )
    (net (code "72") (name "unconnected-(U4-OSCI-Pad27)") (class "Default")
      (node (ref "U4") (pin "27") (pinfunction "OSCI_27") (pintype "passive+no_connect"))
    )
    (net (code "73") (name "unconnected-(U4-OSCO-Pad28)") (class "Default")
      (node (ref "U4") (pin "28") (pinfunction "OSCO_28") (pintype "passive+no_connect"))
    )
    (net (code "74") (name "unconnected-(U4-{slash}CTS-Pad11)") (class "Default")
      (node (ref "U4") (pin "11") (pinfunction "/CTS_11") (pintype "passive+no_connect"))
    )
    (net (code "75") (name "unconnected-(U4-{slash}DCD-Pad10)") (class "Default")
      (node (ref "U4") (pin "10") (pinfunction "/DCD_10") (pintype "passive+no_connect"))
    )
    (net (code "76") (name "unconnected-(U4-{slash}DSR-Pad9)") (class "Default")
      (node (ref "U4") (pin "9") (pinfunction "/DSR_9") (pintype "passive+no_connect"))
    )
    (net (code "77") (name "unconnected-(U4-{slash}DTR-Pad2)") (class "Default")
      (node (ref "U4") (pin "2") (pinfunction "/DTR_2") (pintype "passive+no_connect"))
    )
    (net (code "78") (name "unconnected-(U4-{slash}RESET-Pad19)") (class "Default")
      (node (ref "U4") (pin "19") (pinfunction "/RESET_19") (pintype "passive+no_connect"))
    )
    (net (code "79") (name "unconnected-(U4-{slash}RI-Pad6)") (class "Default")
      (node (ref "U4") (pin "6") (pinfunction "/RI_6") (pintype "passive+no_connect"))
    )
    (net (code "80") (name "unconnected-(U4-{slash}RTS-Pad3)") (class "Default")
      (node (ref "U4") (pin "3") (pinfunction "/RTS_3") (pintype "passive+no_connect"))
    )
  )
)
